# lm7805.net
KiCad netlist of a schematic drawn in Altium Designer
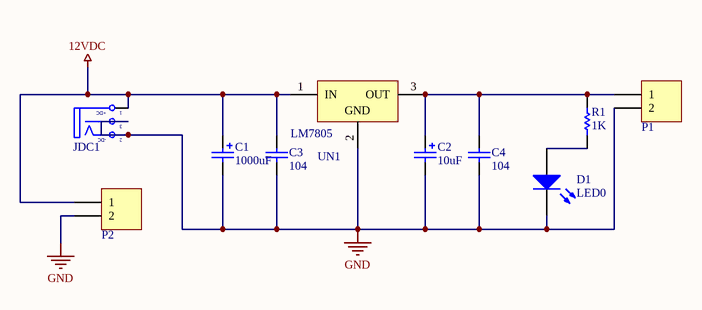
[diagram p0: lm7805.SchDoc]

(export (version "E")
  (design (tool "Eeschema 10.0.6"))
  (components
    (comp (ref "C1")
      (value "1000uF")
      (footprint "CP1/2")
      (description "Polarized Capacitor (Radial)")
      (fields (field (name "Comment") "Cap Pol"))
      (libsource (lib "PIF_Library") (part "Cap Pol"))
    )
    (comp (ref "C2")
      (value "10uF")
      (footprint "CP1/2")
      (description "Polarized Capacitor (Radial)")
      (fields (field (name "Comment") "Cap Pol"))
      (libsource (lib "PIF_Library") (part "Cap Pol"))
    )
    (comp (ref "C3")
      (value "104")
      (footprint "CN1")
      (description "Capacitor")
      (fields (field (name "Comment") "Cap Non-Pol"))
      (libsource (lib "PIF_Library") (part "Cap Non-Pol"))
    )
    (comp (ref "C4")
      (value "104")
      (footprint "CN1")
      (description "Capacitor")
      (fields (field (name "Comment") "Cap Non-Pol"))
      (libsource (lib "PIF_Library") (part "Cap Non-Pol"))
    )
    (comp (ref "D1")
      (value "LED0")
      (footprint "LED-0")
      (description "Typical INFRARED GaAs LED")
      (fields (field (name "PUBLISHER") "Altium Limited"))
      (libsource (lib "Miscellaneous Devices") (part "LED0"))
    )
    (comp (ref "JDC1")
      (value "Jack DC")
      (footprint "DC-IN")
      (description "Jack DC input")
      (libsource (lib "PIF_Library") (part "Jack DC"))
    )
    (comp (ref "P1")
      (value "Header 2")
      (footprint "JP2")
      (description "Header, 2-Pin")
      (fields (field (name "PUBLISHER") "Altium Limited"))
      (libsource (lib "PIF_Library") (part "Header 2"))
    )
    (comp (ref "P2")
      (value "Domino 2")
      (footprint "DOMINO 2- 5mm")
      (description "Domino, 2-Pin")
      (fields (field (name "PUBLISHER") "Altium Limited"))
      (libsource (lib "PIF_Library") (part "Domino 2"))
    )
    (comp (ref "R1")
      (value "1K")
      (footprint "RES 1/2W")
      (description "Resistor")
      (fields (field (name "Comment") "RESISTOR"))
      (libsource (lib "PIF_Library") (part "RESISTOR"))
    )
    (comp (ref "UN1")
      (value "LM7805")
      (footprint "QTO-220")
      (description "Positive Voltage Regulator")
      (libsource (lib "PIF_Library") (part "LM7805"))
    )
  )
  (nets
    (net (code "1") (name "12VDC") (class "Default")
      (node (ref "C1") (pin "1") (pinfunction "1_1") (pintype "passive"))
      (node (ref "C3") (pin "2") (pinfunction "2_2") (pintype "passive"))
      (node (ref "JDC1") (pin "1") (pinfunction "T_1") (pintype "passive"))
      (node (ref "P2") (pin "1") (pinfunction "1_1") (pintype "passive"))
      (node (ref "UN1") (pin "1") (pinfunction "IN_1") (pintype "power_in"))
    )
    (net (code "2") (name "GND") (class "Default")
      (node (ref "C1") (pin "2") (pinfunction "2_2") (pintype "passive"))
      (node (ref "C2") (pin "2") (pinfunction "2_2") (pintype "passive"))
      (node (ref "C3") (pin "1") (pinfunction "1_1") (pintype "passive"))
      (node (ref "C4") (pin "1") (pinfunction "1_1") (pintype "passive"))
      (node (ref "D1") (pin "2") (pinfunction "K_2") (pintype "passive"))
      (node (ref "JDC1") (pin "2") (pinfunction "TN_2") (pintype "passive"))
      (node (ref "JDC1") (pin "3") (pinfunction "S_3") (pintype "power_in"))
      (node (ref "P1") (pin "2") (pinfunction "2_2") (pintype "passive"))
      (node (ref "P2") (pin "2") (pinfunction "2_2") (pintype "passive"))
      (node (ref "UN1") (pin "2") (pinfunction "GND_2") (pintype "power_in"))
    )
    (net (code "3") (name "Net-(D1-A)") (class "Default")
      (node (ref "D1") (pin "1") (pinfunction "A_1") (pintype "passive"))
      (node (ref "R1") (pin "1") (pinfunction "1_1") (pintype "passive"))
    )
    (net (code "4") (name "Net-(UN1-OUT)") (class "Default")
      (node (ref "C2") (pin "1") (pinfunction "1_1") (pintype "passive"))
      (node (ref "C4") (pin "2") (pinfunction "2_2") (pintype "passive"))
      (node (ref "P1") (pin "1") (pinfunction "1_1") (pintype "passive"))
      (node (ref "R1") (pin "2") (pinfunction "2_2") (pintype "passive"))
      (node (ref "UN1") (pin "3") (pinfunction "OUT_3") (pintype "power_in"))
    )
  )
)
